# USB_OTG_FS.net
KiCad netlist of a schematic drawn in Altium Designer
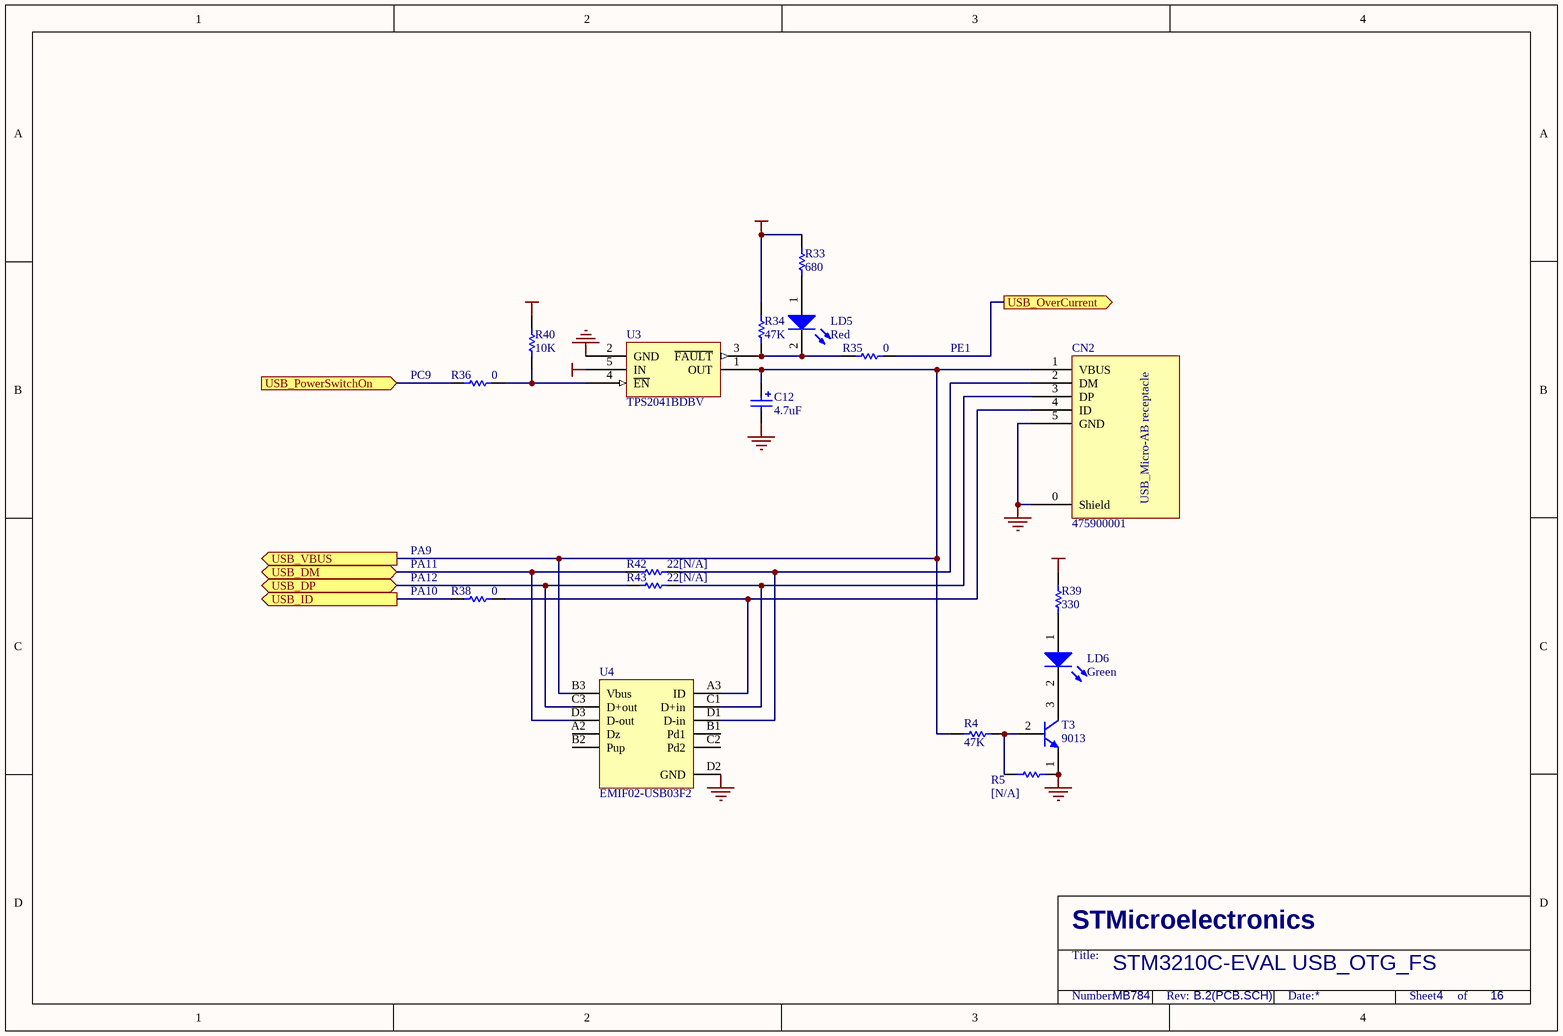
[diagram p0: USB_OTG_FS.SchDoc]

(export (version "E")
  (design (tool "Eeschema 10.0.6"))
  (components
    (comp (ref "C12")
      (value "4.7uF")
      (footprint "TAN-A")
      (description "Polarized Capacitor (Radial)")
      (fields (field (name "PUBLISHER") "Altium Limited"))
      (libsource (lib "Miscellaneous Devices") (part "Cap Pol1"))
    )
    (comp (ref "CN2")
      (value "475900001")
      (footprint "USB-MICRO-AB")
      (libsource (lib "MB786") (part "475900001"))
    )
    (comp (ref "LD5")
      (value "Red")
      (footprint "0603D")
      (description "Typical RED, GREEN, YELLOW, AMBER GaAs LED")
      (fields (field (name "PUBLISHER") "Altium Limited"))
      (libsource (lib "Miscellaneous Devices") (part "LED2"))
    )
    (comp (ref "LD6")
      (value "Green")
      (footprint "0603D")
      (description "Typical RED, GREEN, YELLOW, AMBER GaAs LED")
      (fields (field (name "PUBLISHER") "Altium Limited"))
      (libsource (lib "Miscellaneous Devices") (part "LED2"))
    )
    (comp (ref "R4")
      (value "47K")
      (footprint "0603R")
      (description "Resistor")
      (fields (field (name "PUBLISHER") "Altium Limited"))
      (libsource (lib "Miscellaneous Devices") (part "res1"))
    )
    (comp (ref "R5")
      (value "[N/A]")
      (footprint "0603R")
      (description "Resistor")
      (fields (field (name "PUBLISHER") "Altium Limited"))
      (libsource (lib "Miscellaneous Devices") (part "res1"))
    )
    (comp (ref "R33")
      (value "680")
      (footprint "0603R")
      (description "Resistor")
      (fields (field (name "PUBLISHER") "Altium Limited"))
      (libsource (lib "Miscellaneous Devices") (part "Res1"))
    )
    (comp (ref "R34")
      (value "47K")
      (footprint "0603R")
      (description "Resistor")
      (fields (field (name "PUBLISHER") "Altium Limited"))
      (libsource (lib "Miscellaneous Devices") (part "res1"))
    )
    (comp (ref "R35")
      (value "0")
      (footprint "0603R")
      (description "Resistor")
      (fields (field (name "PUBLISHER") "Altium Limited"))
      (libsource (lib "Miscellaneous Devices") (part "Res1"))
    )
    (comp (ref "R36")
      (value "0")
      (footprint "0603R")
      (description "Resistor")
      (fields (field (name "PUBLISHER") "Altium Limited"))
      (libsource (lib "Miscellaneous Devices") (part "Res1"))
    )
    (comp (ref "R38")
      (value "0")
      (footprint "0603R")
      (description "Resistor")
      (fields (field (name "PUBLISHER") "Altium Limited"))
      (libsource (lib "Miscellaneous Devices") (part "Res1"))
    )
    (comp (ref "R39")
      (value "330")
      (footprint "0603R")
      (description "Resistor")
      (fields (field (name "PUBLISHER") "Altium Limited"))
      (libsource (lib "Miscellaneous Devices") (part "res1"))
    )
    (comp (ref "R40")
      (value "10K")
      (footprint "0603R")
      (description "Resistor")
      (fields (field (name "PUBLISHER") "Altium Limited"))
      (libsource (lib "Miscellaneous Devices") (part "res1"))
    )
    (comp (ref "R42")
      (value "22[N/A]")
      (footprint "0603R")
      (description "Resistor")
      (fields (field (name "PUBLISHER") "Altium Limited"))
      (libsource (lib "Miscellaneous Devices") (part "Res1"))
    )
    (comp (ref "R43")
      (value "22[N/A]")
      (footprint "0603R")
      (description "Resistor")
      (fields (field (name "PUBLISHER") "Altium Limited"))
      (libsource (lib "Miscellaneous Devices") (part "Res1"))
    )
    (comp (ref "T3")
      (value "9013")
      (footprint "SOT-23")
      (description "NPN Bipolar Transistor")
      (fields (field (name "PUBLISHER") "Altium Limited"))
      (libsource (lib "Miscellaneous Devices") (part "NPN"))
    )
    (comp (ref "U3")
      (value "TPS2041BDBV")
      (footprint "SOT-23-5L")
      (libsource (lib "MB784") (part "STMPS2141STR"))
    )
    (comp (ref "U4")
      (value "EMIF02-USB03F2")
      (footprint "FlipChip(11)")
      (libsource (lib "MB784") (part "EMIF02-USB03F2"))
    )
  )
  (nets
    (net (code "1") (name "+3V3") (class "Default")
      (node (ref "R33") (pin "2") (pinfunction "2_2") (pintype "passive"))
      (node (ref "R34") (pin "1") (pinfunction "1_1") (pintype "passive"))
      (node (ref "R39") (pin "2") (pinfunction "2_2") (pintype "passive"))
      (node (ref "R40") (pin "1") (pinfunction "1_1") (pintype "passive"))
    )
    (net (code "2") (name "+5V") (class "Default")
      (node (ref "U3") (pin "5") (pinfunction "IN_5") (pintype "passive"))
    )
    (net (code "3") (name "/USB_DM") (class "Default")
      (node (ref "R42") (pin "2") (pinfunction "2_2") (pintype "passive"))
      (node (ref "U4") (pin "D3") (pinfunction "D-out_D3") (pintype "passive"))
    )
    (net (code "4") (name "/USB_DP") (class "Default")
      (node (ref "R43") (pin "2") (pinfunction "2_2") (pintype "passive"))
      (node (ref "U4") (pin "C3") (pinfunction "D+out_C3") (pintype "passive"))
    )
    (net (code "5") (name "/USB_ID") (class "Default")
      (node (ref "R38") (pin "2") (pinfunction "2_2") (pintype "passive"))
    )
    (net (code "6") (name "/USB_OverCurrent") (class "Default")
      (node (ref "R35") (pin "1") (pinfunction "1_1") (pintype "passive"))
    )
    (net (code "7") (name "/USB_PowerSwitchOn") (class "Default")
      (node (ref "R36") (pin "2") (pinfunction "2_2") (pintype "passive"))
    )
    (net (code "8") (name "/USB_VBUS") (class "Default")
      (node (ref "C12") (pin "1") (pinfunction "1_1") (pintype "passive"))
      (node (ref "CN2") (pin "1") (pinfunction "VBUS_1") (pintype "passive"))
      (node (ref "R4") (pin "2") (pinfunction "2_2") (pintype "passive"))
      (node (ref "U3") (pin "1") (pinfunction "OUT_1") (pintype "passive"))
      (node (ref "U4") (pin "B3") (pinfunction "Vbus_B3") (pintype "passive"))
    )
    (net (code "9") (name "GND") (class "Default")
      (node (ref "C12") (pin "2") (pinfunction "2_2") (pintype "passive"))
      (node (ref "CN2") (pin "0") (pinfunction "Shield_0") (pintype "passive"))
      (node (ref "CN2") (pin "5") (pinfunction "GND_5") (pintype "passive"))
      (node (ref "R5") (pin "1") (pinfunction "1_1") (pintype "passive"))
      (node (ref "T3") (pin "1") (pinfunction "E_1") (pintype "passive"))
      (node (ref "U3") (pin "2") (pinfunction "GND_2") (pintype "passive"))
      (node (ref "U4") (pin "D2") (pinfunction "GND_D2") (pintype "passive"))
    )
    (net (code "10") (name "Net-(CN2-DM)") (class "Default")
      (node (ref "CN2") (pin "2") (pinfunction "DM_2") (pintype "passive"))
      (node (ref "R42") (pin "1") (pinfunction "1_1") (pintype "passive"))
      (node (ref "U4") (pin "D1") (pinfunction "D-in_D1") (pintype "passive"))
    )
    (net (code "11") (name "Net-(CN2-DP)") (class "Default")
      (node (ref "CN2") (pin "3") (pinfunction "DP_3") (pintype "passive"))
      (node (ref "R43") (pin "1") (pinfunction "1_1") (pintype "passive"))
      (node (ref "U4") (pin "C1") (pinfunction "D+in_C1") (pintype "passive"))
    )
    (net (code "12") (name "Net-(CN2-ID)") (class "Default")
      (node (ref "CN2") (pin "4") (pinfunction "ID_4") (pintype "passive"))
      (node (ref "R38") (pin "1") (pinfunction "1_1") (pintype "passive"))
      (node (ref "U4") (pin "A3") (pinfunction "ID_A3") (pintype "passive"))
    )
    (net (code "13") (name "Net-(LD5-A)") (class "Default")
      (node (ref "LD5") (pin "1") (pinfunction "A_1") (pintype "passive"))
      (node (ref "R33") (pin "1") (pinfunction "1_1") (pintype "passive"))
    )
    (net (code "14") (name "Net-(LD5-K)") (class "Default")
      (node (ref "LD5") (pin "2") (pinfunction "K_2") (pintype "passive"))
      (node (ref "R34") (pin "2") (pinfunction "2_2") (pintype "passive"))
      (node (ref "R35") (pin "2") (pinfunction "2_2") (pintype "passive"))
      (node (ref "U3") (pin "3") (pinfunction "~{FAULT}_3") (pintype "output"))
    )
    (net (code "15") (name "Net-(LD6-A)") (class "Default")
      (node (ref "LD6") (pin "1") (pinfunction "A_1") (pintype "passive"))
      (node (ref "R39") (pin "1") (pinfunction "1_1") (pintype "passive"))
    )
    (net (code "16") (name "Net-(LD6-K)") (class "Default")
      (node (ref "LD6") (pin "2") (pinfunction "K_2") (pintype "passive"))
      (node (ref "T3") (pin "3") (pinfunction "C_3") (pintype "passive"))
    )
    (net (code "17") (name "Net-(T3-B)") (class "Default")
      (node (ref "R4") (pin "1") (pinfunction "1_1") (pintype "passive"))
      (node (ref "R5") (pin "2") (pinfunction "2_2") (pintype "passive"))
      (node (ref "T3") (pin "2") (pinfunction "B_2") (pintype "passive"))
    )
    (net (code "18") (name "Net-(U3-~{EN})") (class "Default")
      (node (ref "R36") (pin "1") (pinfunction "1_1") (pintype "passive"))
      (node (ref "R40") (pin "2") (pinfunction "2_2") (pintype "passive"))
      (node (ref "U3") (pin "4") (pinfunction "~{EN}_4") (pintype "input"))
    )
    (net (code "19") (name "unconnected-(U4-Dz-PadA2)") (class "Default")
      (node (ref "U4") (pin "A2") (pinfunction "Dz_A2") (pintype "passive"))
    )
    (net (code "20") (name "unconnected-(U4-Pd1-PadB1)") (class "Default")
      (node (ref "U4") (pin "B1") (pinfunction "Pd1_B1") (pintype "passive"))
    )
    (net (code "21") (name "unconnected-(U4-Pd2-PadC2)") (class "Default")
      (node (ref "U4") (pin "C2") (pinfunction "Pd2_C2") (pintype "passive"))
    )
    (net (code "22") (name "unconnected-(U4-Pup-PadB2)") (class "Default")
      (node (ref "U4") (pin "B2") (pinfunction "Pup_B2") (pintype "passive"))
    )
  )
)
